# Terrarium.net
KiCad netlist of a schematic drawn in EAGLE
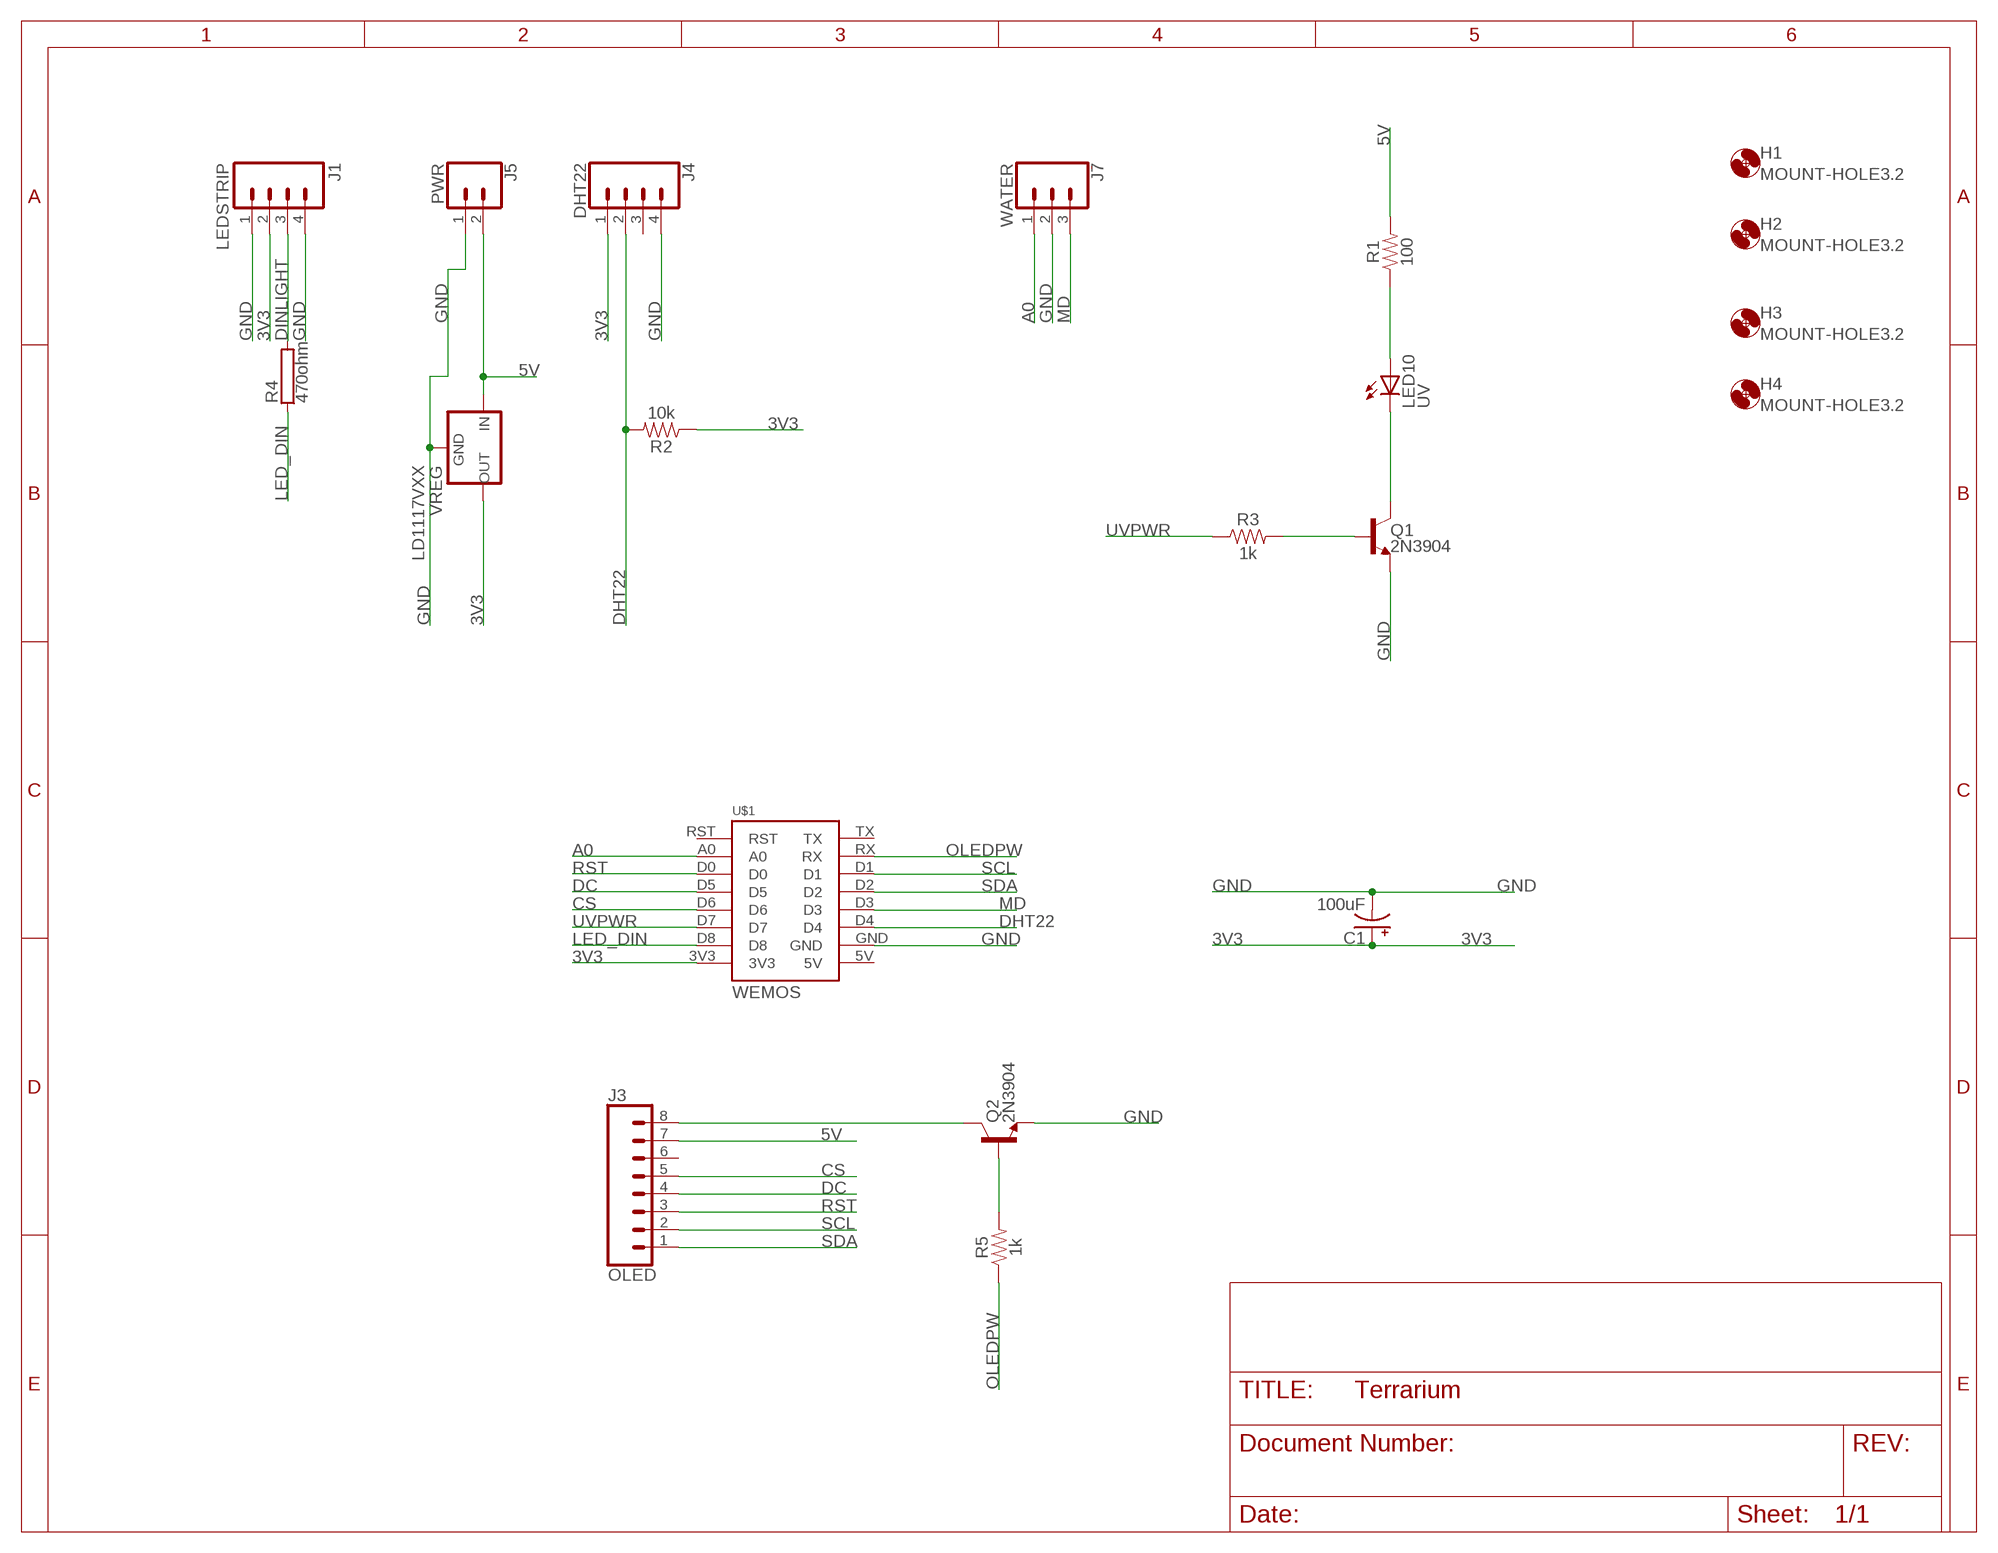
[diagram p0: schematic, sheet 1]

(export (version "E")
  (design (tool "Eeschema 10.0.6"))
  (components
    (comp (ref "C1")
      (value "100uF")
      (footprint "eagle-import:CPOL-RADIAL-2.5MM-6.5MM")
      (libsource (lib "eagle-import") (part "100UF-POLAR-RADIAL-2.5MM-25V-20%"))
    )
    (comp (ref "H1")
      (value "MOUNT-HOLE3.2")
      (footprint "eagle-import:3,2")
      (libsource (lib "eagle-import") (part "MOUNT-HOLE3.2"))
    )
    (comp (ref "H2")
      (value "MOUNT-HOLE3.2")
      (footprint "eagle-import:3,2")
      (libsource (lib "eagle-import") (part "MOUNT-HOLE3.2"))
    )
    (comp (ref "H3")
      (value "MOUNT-HOLE3.2")
      (footprint "eagle-import:3,2")
      (libsource (lib "eagle-import") (part "MOUNT-HOLE3.2"))
    )
    (comp (ref "H4")
      (value "MOUNT-HOLE3.2")
      (footprint "eagle-import:3,2")
      (libsource (lib "eagle-import") (part "MOUNT-HOLE3.2"))
    )
    (comp (ref "J1")
      (value "LEDSTRIP")
      (footprint "eagle-import:1X04@1")
      (libsource (lib "eagle-import") (part "M04PTH"))
    )
    (comp (ref "J3")
      (value "OLED")
      (footprint "eagle-import:1X08")
      (libsource (lib "eagle-import") (part "CONN_08{dblquote}"))
    )
    (comp (ref "J4")
      (value "DHT22")
      (footprint "eagle-import:1X04")
      (libsource (lib "eagle-import") (part "CONN_04"))
    )
    (comp (ref "J5")
      (value "PWR")
      (footprint "eagle-import:1X02")
      (libsource (lib "eagle-import") (part "CONN_02"))
    )
    (comp (ref "J7")
      (value "WATER")
      (footprint "eagle-import:1X03")
      (libsource (lib "eagle-import") (part "CONN_03"))
    )
    (comp (ref "LED10")
      (value "UV")
      (footprint "eagle-import:LED5MM")
      (libsource (lib "eagle-import") (part "LED5MM"))
    )
    (comp (ref "Q1")
      (value "2N3904")
      (footprint "eagle-import:TO-92")
      (libsource (lib "eagle-import") (part "TRANS_NPN-2N3904"))
    )
    (comp (ref "Q2")
      (value "2N3904")
      (footprint "eagle-import:TO-92")
      (libsource (lib "eagle-import") (part "TRANS_NPN-2N3904"))
    )
    (comp (ref "R1")
      (value "100")
      (footprint "eagle-import:AXIAL-0.3")
      (libsource (lib "eagle-import") (part "100OHM-HORIZ-1/4W-1%"))
    )
    (comp (ref "R2")
      (value "10k")
      (footprint "eagle-import:AXIAL-0.3")
      (libsource (lib "eagle-import") (part "10KOHM-HORIZ-1/4W-5%"))
    )
    (comp (ref "R3")
      (value "1k")
      (footprint "eagle-import:AXIAL-0.3")
      (libsource (lib "eagle-import") (part "1KOHM-HORIZ-1/4W-5%"))
    )
    (comp (ref "R4")
      (value "470ohm")
      (footprint "eagle-import:RS1_4")
      (fields (field (name "MF") "OHMITE") (field (name "MPN") "RRS1K0"))
      (libsource (lib "eagle-import") (part "RRS1/4"))
    )
    (comp (ref "R5")
      (value "1k")
      (footprint "eagle-import:AXIAL-0.3")
      (libsource (lib "eagle-import") (part "1KOHM-HORIZ-1/4W-5%"))
    )
    (comp (ref "U$1")
      (value "WEMOS")
      (footprint "eagle-import:WEMOS")
      (libsource (lib "eagle-import") (part "WEMOS"))
    )
    (comp (ref "VREG")
      (value "LD1117VXX")
      (footprint "eagle-import:78XXL")
      (libsource (lib "eagle-import") (part "V_REG_LD1117VXX"))
    )
  )
  (nets
    (net (code "1") (name "/3V3") (class "Default")
      (node (ref "C1") (pin "1") (pinfunction "+_1") (pintype "passive"))
      (node (ref "J1") (pin "2") (pinfunction "2_2") (pintype "passive"))
      (node (ref "J4") (pin "1") (pinfunction "1_1") (pintype "passive"))
      (node (ref "R2") (pin "P$1") (pinfunction "1_P$1") (pintype "passive"))
      (node (ref "U$1") (pin "3V3") (pinfunction "3V3_3V3") (pintype "bidirectional"))
      (node (ref "VREG") (pin "GND") (pinfunction "OUT_GND") (pintype "passive"))
    )
    (net (code "2") (name "/5V") (class "Default")
      (node (ref "J3") (pin "7") (pinfunction "7_7") (pintype "passive"))
      (node (ref "J5") (pin "2") (pinfunction "2_2") (pintype "passive"))
      (node (ref "R1") (pin "P$2") (pinfunction "2_P$2") (pintype "passive"))
      (node (ref "VREG") (pin "OUT") (pinfunction "IN_OUT") (pintype "input"))
    )
    (net (code "3") (name "/A0") (class "Default")
      (node (ref "J7") (pin "1") (pinfunction "1_1") (pintype "passive"))
      (node (ref "U$1") (pin "A0") (pinfunction "A0_A0") (pintype "bidirectional"))
    )
    (net (code "4") (name "/CS") (class "Default")
      (node (ref "J3") (pin "5") (pinfunction "5_5") (pintype "passive"))
      (node (ref "U$1") (pin "D6") (pinfunction "D6_D6") (pintype "bidirectional"))
    )
    (net (code "5") (name "/DC") (class "Default")
      (node (ref "J3") (pin "4") (pinfunction "4_4") (pintype "passive"))
      (node (ref "U$1") (pin "D5") (pinfunction "D5_D5") (pintype "bidirectional"))
    )
    (net (code "6") (name "/DHT22") (class "Default")
      (node (ref "J4") (pin "2") (pinfunction "2_2") (pintype "passive"))
      (node (ref "R2") (pin "P$2") (pinfunction "2_P$2") (pintype "passive"))
      (node (ref "U$1") (pin "D4") (pinfunction "D4_D4") (pintype "bidirectional"))
    )
    (net (code "7") (name "/DINLIGHT") (class "Default")
      (node (ref "J1") (pin "3") (pinfunction "3_3") (pintype "passive"))
      (node (ref "R4") (pin "2") (pinfunction "2_2") (pintype "passive"))
    )
    (net (code "8") (name "/GND") (class "Default")
      (node (ref "C1") (pin "2") (pinfunction "-_2") (pintype "passive"))
      (node (ref "J1") (pin "1") (pinfunction "1_1") (pintype "passive"))
      (node (ref "J1") (pin "4") (pinfunction "4_4") (pintype "passive"))
      (node (ref "J4") (pin "4") (pinfunction "4_4") (pintype "passive"))
      (node (ref "J5") (pin "1") (pinfunction "1_1") (pintype "passive"))
      (node (ref "J7") (pin "2") (pinfunction "2_2") (pintype "passive"))
      (node (ref "Q1") (pin "1") (pinfunction "E_1") (pintype "passive"))
      (node (ref "Q2") (pin "1") (pinfunction "E_1") (pintype "passive"))
      (node (ref "U$1") (pin "GND") (pinfunction "GND_GND") (pintype "bidirectional"))
      (node (ref "VREG") (pin "IN") (pinfunction "GND_IN") (pintype "input"))
    )
    (net (code "9") (name "/LED_DIN") (class "Default")
      (node (ref "R4") (pin "1") (pinfunction "1_1") (pintype "passive"))
      (node (ref "U$1") (pin "D8") (pinfunction "D8_D8") (pintype "bidirectional"))
    )
    (net (code "10") (name "/MD") (class "Default")
      (node (ref "J7") (pin "3") (pinfunction "3_3") (pintype "passive"))
      (node (ref "U$1") (pin "D3") (pinfunction "D3_D3") (pintype "bidirectional"))
    )
    (net (code "11") (name "/OLEDPW") (class "Default")
      (node (ref "R5") (pin "P$1") (pinfunction "1_P$1") (pintype "passive"))
      (node (ref "U$1") (pin "RX") (pinfunction "RX_RX") (pintype "bidirectional"))
    )
    (net (code "12") (name "/RST") (class "Default")
      (node (ref "J3") (pin "3") (pinfunction "3_3") (pintype "passive"))
      (node (ref "U$1") (pin "D0") (pinfunction "D0_D0") (pintype "bidirectional"))
    )
    (net (code "13") (name "/SCL") (class "Default")
      (node (ref "J3") (pin "2") (pinfunction "2_2") (pintype "passive"))
      (node (ref "U$1") (pin "D1") (pinfunction "D1_D1") (pintype "bidirectional"))
    )
    (net (code "14") (name "/SDA") (class "Default")
      (node (ref "J3") (pin "1") (pinfunction "1_1") (pintype "passive"))
      (node (ref "U$1") (pin "D2") (pinfunction "D2_D2") (pintype "bidirectional"))
    )
    (net (code "15") (name "/UVPWR") (class "Default")
      (node (ref "R3") (pin "P$1") (pinfunction "1_P$1") (pintype "passive"))
      (node (ref "U$1") (pin "D7") (pinfunction "D7_D7") (pintype "bidirectional"))
    )
    (net (code "16") (name "Net-(LED10-C)") (class "Default")
      (node (ref "LED10") (pin "K") (pinfunction "C_K") (pintype "passive"))
      (node (ref "Q1") (pin "3") (pinfunction "C_3") (pintype "passive"))
    )
    (net (code "17") (name "Net-(Q1-B)") (class "Default")
      (node (ref "Q1") (pin "2") (pinfunction "B_2") (pintype "passive"))
      (node (ref "R3") (pin "P$2") (pinfunction "2_P$2") (pintype "passive"))
    )
    (net (code "18") (name "Net-(Q2-B)") (class "Default")
      (node (ref "Q2") (pin "2") (pinfunction "B_2") (pintype "passive"))
      (node (ref "R5") (pin "P$2") (pinfunction "2_P$2") (pintype "passive"))
    )
    (net (code "19") (name "Net-(Q2-C)") (class "Default")
      (node (ref "J3") (pin "8") (pinfunction "8_8") (pintype "passive"))
      (node (ref "Q2") (pin "3") (pinfunction "C_3") (pintype "passive"))
    )
    (net (code "20") (name "Net-(R1-1)") (class "Default")
      (node (ref "LED10") (pin "A") (pinfunction "A_A") (pintype "passive"))
      (node (ref "R1") (pin "P$1") (pinfunction "1_P$1") (pintype "passive"))
    )
    (net (code "21") (name "unconnected-(J3-Pad6)") (class "Default")
      (node (ref "J3") (pin "6") (pinfunction "6_6") (pintype "passive"))
    )
    (net (code "22") (name "unconnected-(J4-Pad3)") (class "Default")
      (node (ref "J4") (pin "3") (pinfunction "3_3") (pintype "passive"))
    )
    (net (code "23") (name "unconnected-(U$1-Pad5V)") (class "Default")
      (node (ref "U$1") (pin "5V") (pinfunction "5V_5V") (pintype "bidirectional"))
    )
    (net (code "24") (name "unconnected-(U$1-PadRST)") (class "Default")
      (node (ref "U$1") (pin "RST") (pinfunction "RST_RST") (pintype "bidirectional"))
    )
    (net (code "25") (name "unconnected-(U$1-PadTX)") (class "Default")
      (node (ref "U$1") (pin "TX") (pinfunction "TX_TX") (pintype "bidirectional"))
    )
  )
)
